# RoverWing-cover-V1_5.net
KiCad netlist of a schematic drawn in EAGLE
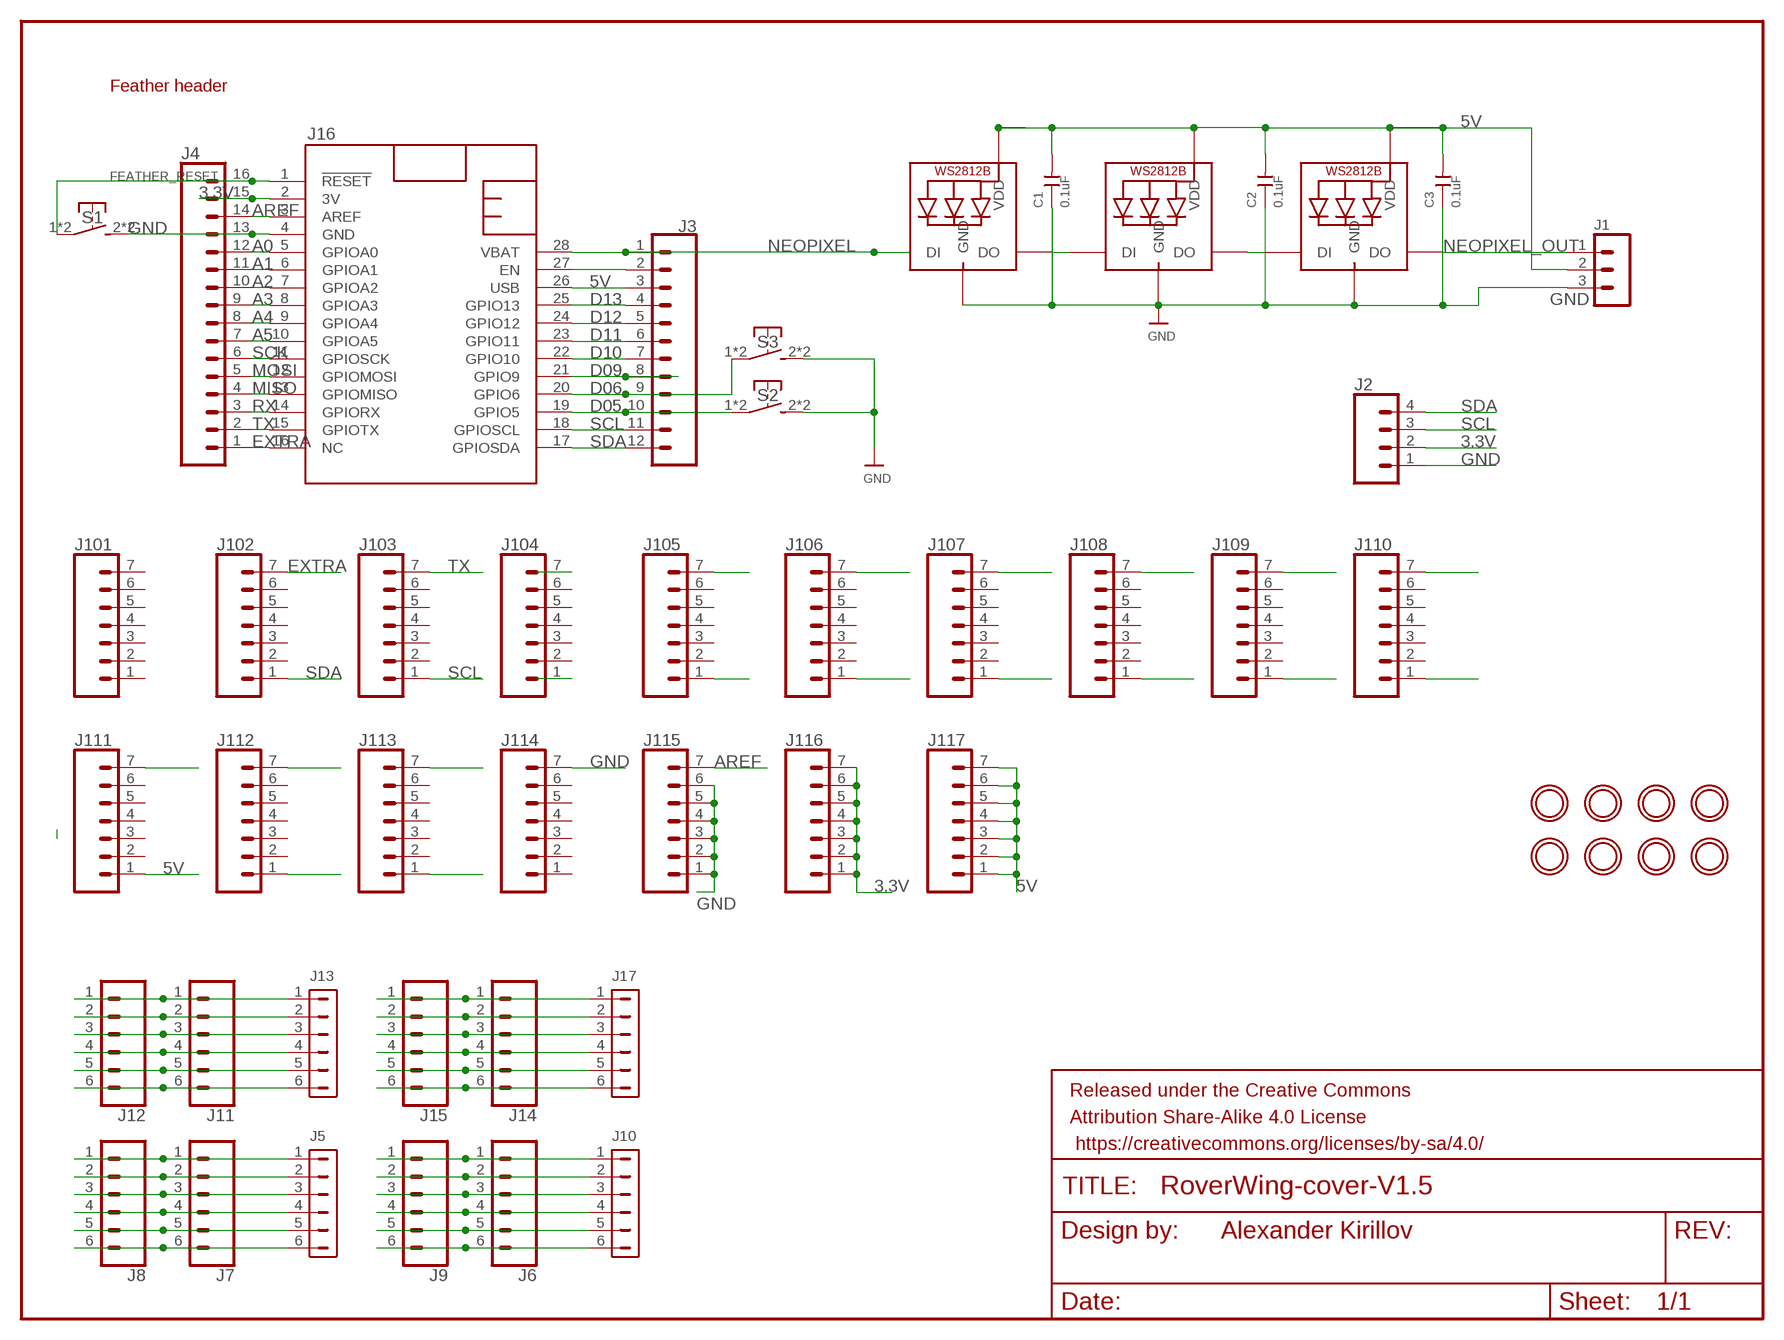
[diagram p0: schematic, sheet 1]

(export (version "E")
  (design (tool "Eeschema 10.0.6"))
  (components
    (comp (ref "C1")
      (value "0.1uF")
      (footprint "eagle-import:C0805")
      (libsource (lib "eagle-import") (part "CAP-CERAMIC-SMD-0805"))
    )
    (comp (ref "C2")
      (value "0.1uF")
      (footprint "eagle-import:C0805")
      (libsource (lib "eagle-import") (part "CAP-CERAMIC-SMD-0805"))
    )
    (comp (ref "C3")
      (value "0.1uF")
      (footprint "eagle-import:C0805")
      (libsource (lib "eagle-import") (part "CAP-CERAMIC-SMD-0805"))
    )
    (comp (ref "FRAME2")
      (value "FRAME-LETTERNO_PACKAGE")
      (footprint "eagle-import:DUMMY")
      (fields (field (name "DESIGNER") "Nobody"))
      (libsource (lib "eagle-import") (part "FRAME-LETTERNO_PACKAGE"))
    )
    (comp (ref "J1")
      (value "HEADER-PH-3PSIDEENTRY")
      (footprint "eagle-import:S3B-PH-K")
      (fields (field (name "PARTNO") "S3B-PH-K-S(LF)(SN)"))
      (libsource (lib "eagle-import") (part "HEADER-PH-3PSIDEENTRY"))
    )
    (comp (ref "J2")
      (value "CONN_04")
      (footprint "eagle-import:1X04")
      (libsource (lib "eagle-import") (part "CONN_04"))
    )
    (comp (ref "J3")
      (value "CONN_12NO_SILK")
      (footprint "eagle-import:1X12_NO_SILK")
      (libsource (lib "eagle-import") (part "CONN_12NO_SILK"))
    )
    (comp (ref "J4")
      (value "CONN_161X16_NO_SILK")
      (footprint "eagle-import:1X16_NO_SILK")
      (libsource (lib "eagle-import") (part "CONN_161X16_NO_SILK"))
    )
    (comp (ref "J5")
      (value "HEADER-PH-6PSIDEENTRY")
      (footprint "eagle-import:S6B-PH-K")
      (libsource (lib "eagle-import") (part "HEADER-PH-6PSIDEENTRY"))
    )
    (comp (ref "J6")
      (value "CONN_06NO_SILK_NO_POP")
      (footprint "eagle-import:1X06_NO_SILK")
      (libsource (lib "eagle-import") (part "CONN_06NO_SILK_NO_POP"))
    )
    (comp (ref "J7")
      (value "CONN_06NO_SILK_NO_POP")
      (footprint "eagle-import:1X06_NO_SILK")
      (libsource (lib "eagle-import") (part "CONN_06NO_SILK_NO_POP"))
    )
    (comp (ref "J8")
      (value "CONN_06NO_SILK_NO_POP")
      (footprint "eagle-import:1X06_NO_SILK")
      (libsource (lib "eagle-import") (part "CONN_06NO_SILK_NO_POP"))
    )
    (comp (ref "J9")
      (value "CONN_06NO_SILK_NO_POP")
      (footprint "eagle-import:1X06_NO_SILK")
      (libsource (lib "eagle-import") (part "CONN_06NO_SILK_NO_POP"))
    )
    (comp (ref "J10")
      (value "HEADER-PH-6PSIDEENTRY")
      (footprint "eagle-import:S6B-PH-K")
      (libsource (lib "eagle-import") (part "HEADER-PH-6PSIDEENTRY"))
    )
    (comp (ref "J11")
      (value "CONN_06NO_SILK_NO_POP")
      (footprint "eagle-import:1X06_NO_SILK")
      (libsource (lib "eagle-import") (part "CONN_06NO_SILK_NO_POP"))
    )
    (comp (ref "J12")
      (value "CONN_06NO_SILK_NO_POP")
      (footprint "eagle-import:1X06_NO_SILK")
      (libsource (lib "eagle-import") (part "CONN_06NO_SILK_NO_POP"))
    )
    (comp (ref "J13")
      (value "HEADER-PH-6PSIDEENTRY")
      (footprint "eagle-import:S6B-PH-K")
      (libsource (lib "eagle-import") (part "HEADER-PH-6PSIDEENTRY"))
    )
    (comp (ref "J14")
      (value "CONN_06NO_SILK_NO_POP")
      (footprint "eagle-import:1X06_NO_SILK")
      (libsource (lib "eagle-import") (part "CONN_06NO_SILK_NO_POP"))
    )
    (comp (ref "J15")
      (value "CONN_06NO_SILK_NO_POP")
      (footprint "eagle-import:1X06_NO_SILK")
      (libsource (lib "eagle-import") (part "CONN_06NO_SILK_NO_POP"))
    )
    (comp (ref "J16")
      (value "FEATHERWING_NODIM")
      (footprint "eagle-import:FEATHERWING_DIM")
      (libsource (lib "eagle-import") (part "FEATHERWING_NODIM"))
    )
    (comp (ref "J17")
      (value "HEADER-PH-6PSIDEENTRY")
      (footprint "eagle-import:S6B-PH-K")
      (libsource (lib "eagle-import") (part "HEADER-PH-6PSIDEENTRY"))
    )
    (comp (ref "J101")
      (value "CONN_07NO_SILK")
      (footprint "eagle-import:1X07_NO_SILK")
      (libsource (lib "eagle-import") (part "CONN_07NO_SILK"))
    )
    (comp (ref "J102")
      (value "CONN_07NO_SILK")
      (footprint "eagle-import:1X07_NO_SILK")
      (libsource (lib "eagle-import") (part "CONN_07NO_SILK"))
    )
    (comp (ref "J103")
      (value "CONN_07NO_SILK")
      (footprint "eagle-import:1X07_NO_SILK")
      (libsource (lib "eagle-import") (part "CONN_07NO_SILK"))
    )
    (comp (ref "J104")
      (value "CONN_07NO_SILK")
      (footprint "eagle-import:1X07_NO_SILK")
      (libsource (lib "eagle-import") (part "CONN_07NO_SILK"))
    )
    (comp (ref "J105")
      (value "CONN_07NO_SILK")
      (footprint "eagle-import:1X07_NO_SILK")
      (libsource (lib "eagle-import") (part "CONN_07NO_SILK"))
    )
    (comp (ref "J106")
      (value "CONN_07NO_SILK")
      (footprint "eagle-import:1X07_NO_SILK")
      (libsource (lib "eagle-import") (part "CONN_07NO_SILK"))
    )
    (comp (ref "J107")
      (value "CONN_07NO_SILK")
      (footprint "eagle-import:1X07_NO_SILK")
      (libsource (lib "eagle-import") (part "CONN_07NO_SILK"))
    )
    (comp (ref "J108")
      (value "CONN_07NO_SILK")
      (footprint "eagle-import:1X07_NO_SILK")
      (libsource (lib "eagle-import") (part "CONN_07NO_SILK"))
    )
    (comp (ref "J109")
      (value "CONN_07NO_SILK")
      (footprint "eagle-import:1X07_NO_SILK")
      (libsource (lib "eagle-import") (part "CONN_07NO_SILK"))
    )
    (comp (ref "J110")
      (value "CONN_07NO_SILK")
      (footprint "eagle-import:1X07_NO_SILK")
      (libsource (lib "eagle-import") (part "CONN_07NO_SILK"))
    )
    (comp (ref "J111")
      (value "CONN_07NO_SILK")
      (footprint "eagle-import:1X07_NO_SILK")
      (libsource (lib "eagle-import") (part "CONN_07NO_SILK"))
    )
    (comp (ref "J112")
      (value "CONN_07NO_SILK")
      (footprint "eagle-import:1X07_NO_SILK")
      (libsource (lib "eagle-import") (part "CONN_07NO_SILK"))
    )
    (comp (ref "J113")
      (value "CONN_07NO_SILK")
      (footprint "eagle-import:1X07_NO_SILK")
      (libsource (lib "eagle-import") (part "CONN_07NO_SILK"))
    )
    (comp (ref "J114")
      (value "CONN_07NO_SILK")
      (footprint "eagle-import:1X07_NO_SILK")
      (libsource (lib "eagle-import") (part "CONN_07NO_SILK"))
    )
    (comp (ref "J115")
      (value "CONN_07NO_SILK")
      (footprint "eagle-import:1X07_NO_SILK")
      (libsource (lib "eagle-import") (part "CONN_07NO_SILK"))
    )
    (comp (ref "J116")
      (value "CONN_07NO_SILK")
      (footprint "eagle-import:1X07_NO_SILK")
      (libsource (lib "eagle-import") (part "CONN_07NO_SILK"))
    )
    (comp (ref "J117")
      (value "CONN_07NO_SILK")
      (footprint "eagle-import:1X07_NO_SILK")
      (libsource (lib "eagle-import") (part "CONN_07NO_SILK"))
    )
    (comp (ref "LED1")
      (value "WS2812B5050")
      (footprint "eagle-import:WS2812B")
      (libsource (lib "eagle-import") (part "WS2812B5050"))
    )
    (comp (ref "LED2")
      (value "WS2812B5050")
      (footprint "eagle-import:WS2812B")
      (libsource (lib "eagle-import") (part "WS2812B5050"))
    )
    (comp (ref "LED3")
      (value "WS2812B5050")
      (footprint "eagle-import:WS2812B")
      (libsource (lib "eagle-import") (part "WS2812B5050"))
    )
    (comp (ref "S1")
      (value "SW-TACTILE-4.5X4.5_SMD")
      (footprint "eagle-import:TL3305")
      (libsource (lib "eagle-import") (part "SW-TACTILE-4.5X4.5_SMD"))
    )
    (comp (ref "S2")
      (value "SW-TACTILE-4.5X4.5_SMD")
      (footprint "eagle-import:TL3305")
      (libsource (lib "eagle-import") (part "SW-TACTILE-4.5X4.5_SMD"))
    )
    (comp (ref "S3")
      (value "SW-TACTILE-4.5X4.5_SMD")
      (footprint "eagle-import:TL3305")
      (libsource (lib "eagle-import") (part "SW-TACTILE-4.5X4.5_SMD"))
    )
    (comp (ref "U$3")
      (value "MOUNTINGHOLE3.0_NPH")
      (footprint "eagle-import:MOUNTINGHOLE_3.0_NPH")
      (libsource (lib "eagle-import") (part "MOUNTINGHOLE3.0_NPH"))
    )
    (comp (ref "U$4")
      (value "MOUNTINGHOLE3.0_NPH")
      (footprint "eagle-import:MOUNTINGHOLE_3.0_NPH")
      (libsource (lib "eagle-import") (part "MOUNTINGHOLE3.0_NPH"))
    )
    (comp (ref "U$14")
      (value "MOUNTINGHOLE3.0_NPH")
      (footprint "eagle-import:MOUNTINGHOLE_3.0_NPH")
      (libsource (lib "eagle-import") (part "MOUNTINGHOLE3.0_NPH"))
    )
    (comp (ref "U$15")
      (value "MOUNTINGHOLE3.0_NPH")
      (footprint "eagle-import:MOUNTINGHOLE_3.0_NPH")
      (libsource (lib "eagle-import") (part "MOUNTINGHOLE3.0_NPH"))
    )
    (comp (ref "U$24")
      (value "MOUNTINGHOLE3.0_NPH")
      (footprint "eagle-import:MOUNTINGHOLE_3.0_NPH")
      (libsource (lib "eagle-import") (part "MOUNTINGHOLE3.0_NPH"))
    )
    (comp (ref "U$25")
      (value "MOUNTINGHOLE3.0_NPH")
      (footprint "eagle-import:MOUNTINGHOLE_3.0_NPH")
      (libsource (lib "eagle-import") (part "MOUNTINGHOLE3.0_NPH"))
    )
    (comp (ref "U$26")
      (value "MOUNTINGHOLE3.0_NPH")
      (footprint "eagle-import:MOUNTINGHOLE_3.0_NPH")
      (libsource (lib "eagle-import") (part "MOUNTINGHOLE3.0_NPH"))
    )
    (comp (ref "U$27")
      (value "MOUNTINGHOLE3.0_NPH")
      (footprint "eagle-import:MOUNTINGHOLE_3.0_NPH")
      (libsource (lib "eagle-import") (part "MOUNTINGHOLE3.0_NPH"))
    )
  )
  (nets
    (net (code "1") (name "/3.3V") (class "Default")
      (node (ref "J116") (pin "1") (pinfunction "1_1") (pintype "passive"))
      (node (ref "J116") (pin "2") (pinfunction "2_2") (pintype "passive"))
      (node (ref "J116") (pin "3") (pinfunction "3_3") (pintype "passive"))
      (node (ref "J116") (pin "4") (pinfunction "4_4") (pintype "passive"))
      (node (ref "J116") (pin "5") (pinfunction "5_5") (pintype "passive"))
      (node (ref "J116") (pin "6") (pinfunction "6_6") (pintype "passive"))
      (node (ref "J116") (pin "7") (pinfunction "7_7") (pintype "passive"))
      (node (ref "J16") (pin "2") (pinfunction "3V_2") (pintype "power_in"))
      (node (ref "J2") (pin "2") (pinfunction "2_2") (pintype "passive"))
      (node (ref "J4") (pin "15") (pinfunction "15_15") (pintype "passive"))
    )
    (net (code "2") (name "/5V") (class "Default")
      (node (ref "C1") (pin "2") (pinfunction "2_2") (pintype "passive"))
      (node (ref "C2") (pin "2") (pinfunction "2_2") (pintype "passive"))
      (node (ref "C3") (pin "2") (pinfunction "2_2") (pintype "passive"))
      (node (ref "J1") (pin "2") (pinfunction "2_2") (pintype "passive"))
      (node (ref "J111") (pin "1") (pinfunction "1_1") (pintype "passive"))
      (node (ref "J117") (pin "1") (pinfunction "1_1") (pintype "passive"))
      (node (ref "J117") (pin "2") (pinfunction "2_2") (pintype "passive"))
      (node (ref "J117") (pin "3") (pinfunction "3_3") (pintype "passive"))
      (node (ref "J117") (pin "4") (pinfunction "4_4") (pintype "passive"))
      (node (ref "J117") (pin "5") (pinfunction "5_5") (pintype "passive"))
      (node (ref "J117") (pin "6") (pinfunction "6_6") (pintype "passive"))
      (node (ref "J117") (pin "7") (pinfunction "7_7") (pintype "passive"))
      (node (ref "J16") (pin "26") (pinfunction "USB_26") (pintype "power_in"))
      (node (ref "J3") (pin "3") (pinfunction "3_3") (pintype "passive"))
      (node (ref "LED1") (pin "1-VDD") (pinfunction "VDD_1-VDD") (pintype "power_in"))
      (node (ref "LED2") (pin "1-VDD") (pinfunction "VDD_1-VDD") (pintype "power_in"))
      (node (ref "LED3") (pin "1-VDD") (pinfunction "VDD_1-VDD") (pintype "power_in"))
    )
    (net (code "3") (name "/A0") (class "Default")
      (node (ref "J113") (pin "7") (pinfunction "7_7") (pintype "passive"))
      (node (ref "J16") (pin "5") (pinfunction "GPIOA0_5") (pintype "bidirectional"))
      (node (ref "J4") (pin "12") (pinfunction "12_12") (pintype "passive"))
    )
    (net (code "4") (name "/A1") (class "Default")
      (node (ref "J112") (pin "7") (pinfunction "7_7") (pintype "passive"))
      (node (ref "J16") (pin "6") (pinfunction "GPIOA1_6") (pintype "bidirectional"))
      (node (ref "J4") (pin "11") (pinfunction "11_11") (pintype "passive"))
    )
    (net (code "5") (name "/A2") (class "Default")
      (node (ref "J111") (pin "7") (pinfunction "7_7") (pintype "passive"))
      (node (ref "J16") (pin "7") (pinfunction "GPIOA2_7") (pintype "bidirectional"))
      (node (ref "J4") (pin "10") (pinfunction "10_10") (pintype "passive"))
    )
    (net (code "6") (name "/A3") (class "Default")
      (node (ref "J110") (pin "7") (pinfunction "7_7") (pintype "passive"))
      (node (ref "J16") (pin "8") (pinfunction "GPIOA3_8") (pintype "bidirectional"))
      (node (ref "J4") (pin "9") (pinfunction "9_9") (pintype "passive"))
    )
    (net (code "7") (name "/A4") (class "Default")
      (node (ref "J109") (pin "7") (pinfunction "7_7") (pintype "passive"))
      (node (ref "J16") (pin "9") (pinfunction "GPIOA4_9") (pintype "bidirectional"))
      (node (ref "J4") (pin "8") (pinfunction "8_8") (pintype "passive"))
    )
    (net (code "8") (name "/A5") (class "Default")
      (node (ref "J108") (pin "7") (pinfunction "7_7") (pintype "passive"))
      (node (ref "J16") (pin "10") (pinfunction "GPIOA5_10") (pintype "bidirectional"))
      (node (ref "J4") (pin "7") (pinfunction "7_7") (pintype "passive"))
    )
    (net (code "9") (name "/AREF") (class "Default")
      (node (ref "J115") (pin "7") (pinfunction "7_7") (pintype "passive"))
      (node (ref "J16") (pin "3") (pinfunction "AREF_3") (pintype "passive"))
      (node (ref "J4") (pin "14") (pinfunction "14_14") (pintype "passive"))
    )
    (net (code "10") (name "/D05") (class "Default")
      (node (ref "J104") (pin "1") (pinfunction "1_1") (pintype "passive"))
      (node (ref "J16") (pin "19") (pinfunction "GPIO5_19") (pintype "bidirectional"))
      (node (ref "J3") (pin "10") (pinfunction "10_10") (pintype "passive"))
      (node (ref "S2") (pin "1") (pinfunction "P1_1") (pintype "passive"))
      (node (ref "S2") (pin "4") (pinfunction "P1_4") (pintype "passive"))
    )
    (net (code "11") (name "/D06") (class "Default")
      (node (ref "J105") (pin "1") (pinfunction "1_1") (pintype "passive"))
      (node (ref "J16") (pin "20") (pinfunction "GPIO6_20") (pintype "bidirectional"))
      (node (ref "J3") (pin "9") (pinfunction "9_9") (pintype "passive"))
      (node (ref "S3") (pin "1") (pinfunction "P1_1") (pintype "passive"))
      (node (ref "S3") (pin "4") (pinfunction "P1_4") (pintype "passive"))
    )
    (net (code "12") (name "/D09") (class "Default")
      (node (ref "J106") (pin "1") (pinfunction "1_1") (pintype "passive"))
      (node (ref "J16") (pin "21") (pinfunction "GPIO9_21") (pintype "bidirectional"))
      (node (ref "J3") (pin "8") (pinfunction "8_8") (pintype "passive"))
    )
    (net (code "13") (name "/D10") (class "Default")
      (node (ref "J107") (pin "1") (pinfunction "1_1") (pintype "passive"))
      (node (ref "J16") (pin "22") (pinfunction "GPIO10_22") (pintype "bidirectional"))
      (node (ref "J3") (pin "7") (pinfunction "7_7") (pintype "passive"))
    )
    (net (code "14") (name "/D11") (class "Default")
      (node (ref "J108") (pin "1") (pinfunction "1_1") (pintype "passive"))
      (node (ref "J16") (pin "23") (pinfunction "GPIO11_23") (pintype "bidirectional"))
      (node (ref "J3") (pin "6") (pinfunction "6_6") (pintype "passive"))
    )
    (net (code "15") (name "/D12") (class "Default")
      (node (ref "J109") (pin "1") (pinfunction "1_1") (pintype "passive"))
      (node (ref "J16") (pin "24") (pinfunction "GPIO12_24") (pintype "bidirectional"))
      (node (ref "J3") (pin "5") (pinfunction "5_5") (pintype "passive"))
    )
    (net (code "16") (name "/D13") (class "Default")
      (node (ref "J110") (pin "1") (pinfunction "1_1") (pintype "passive"))
      (node (ref "J16") (pin "25") (pinfunction "GPIO13_25") (pintype "bidirectional"))
      (node (ref "J3") (pin "4") (pinfunction "4_4") (pintype "passive"))
    )
    (net (code "17") (name "/EXTRA") (class "Default")
      (node (ref "J102") (pin "7") (pinfunction "7_7") (pintype "passive"))
      (node (ref "J16") (pin "16") (pinfunction "NC_16") (pintype "passive"))
      (node (ref "J4") (pin "1") (pinfunction "1_1") (pintype "passive"))
    )
    (net (code "18") (name "/FEATHER_RESET") (class "Default")
      (node (ref "J16") (pin "1") (pinfunction "~{RESET}_1") (pintype "input"))
      (node (ref "J4") (pin "16") (pinfunction "16_16") (pintype "passive"))
      (node (ref "S1") (pin "1") (pinfunction "P1_1") (pintype "passive"))
      (node (ref "S1") (pin "4") (pinfunction "P1_4") (pintype "passive"))
    )
    (net (code "19") (name "/MISO") (class "Default")
      (node (ref "J105") (pin "7") (pinfunction "7_7") (pintype "passive"))
      (node (ref "J16") (pin "13") (pinfunction "GPIOMISO_13") (pintype "bidirectional"))
      (node (ref "J4") (pin "4") (pinfunction "4_4") (pintype "passive"))
    )
    (net (code "20") (name "/MOSI") (class "Default")
      (node (ref "J106") (pin "7") (pinfunction "7_7") (pintype "passive"))
      (node (ref "J16") (pin "12") (pinfunction "GPIOMOSI_12") (pintype "bidirectional"))
      (node (ref "J4") (pin "5") (pinfunction "5_5") (pintype "passive"))
    )
    (net (code "21") (name "/N$37") (class "Default")
      (node (ref "J112") (pin "1") (pinfunction "1_1") (pintype "passive"))
      (node (ref "J16") (pin "27") (pinfunction "EN_27") (pintype "passive"))
      (node (ref "J3") (pin "2") (pinfunction "2_2") (pintype "passive"))
    )
    (net (code "22") (name "/NEOPIXEL") (class "Default")
      (node (ref "J16") (pin "28") (pinfunction "VBAT_28") (pintype "power_in"))
      (node (ref "J3") (pin "1") (pinfunction "1_1") (pintype "passive"))
      (node (ref "LED1") (pin "4-DIN") (pinfunction "DI_4-DIN") (pintype "input"))
    )
    (net (code "23") (name "/NEOPIXEL_OUT") (class "Default")
      (node (ref "J1") (pin "1") (pinfunction "1_1") (pintype "passive"))
      (node (ref "LED3") (pin "2-DOUT") (pinfunction "DO_2-DOUT") (pintype "output"))
    )
    (net (code "24") (name "/RX") (class "Default")
      (node (ref "J104") (pin "7") (pinfunction "7_7") (pintype "passive"))
      (node (ref "J16") (pin "14") (pinfunction "GPIORX_14") (pintype "bidirectional"))
      (node (ref "J4") (pin "3") (pinfunction "3_3") (pintype "passive"))
    )
    (net (code "25") (name "/SCK") (class "Default")
      (node (ref "J107") (pin "7") (pinfunction "7_7") (pintype "passive"))
      (node (ref "J16") (pin "11") (pinfunction "GPIOSCK_11") (pintype "bidirectional"))
      (node (ref "J4") (pin "6") (pinfunction "6_6") (pintype "passive"))
    )
    (net (code "26") (name "/SCL") (class "Default")
      (node (ref "J103") (pin "1") (pinfunction "1_1") (pintype "passive"))
      (node (ref "J16") (pin "18") (pinfunction "GPIOSCL_18") (pintype "bidirectional"))
      (node (ref "J2") (pin "3") (pinfunction "3_3") (pintype "passive"))
      (node (ref "J3") (pin "11") (pinfunction "11_11") (pintype "passive"))
    )
    (net (code "27") (name "/SDA") (class "Default")
      (node (ref "J102") (pin "1") (pinfunction "1_1") (pintype "passive"))
      (node (ref "J16") (pin "17") (pinfunction "GPIOSDA_17") (pintype "bidirectional"))
      (node (ref "J2") (pin "4") (pinfunction "4_4") (pintype "passive"))
      (node (ref "J3") (pin "12") (pinfunction "12_12") (pintype "passive"))
    )
    (net (code "28") (name "/TX") (class "Default")
      (node (ref "J103") (pin "7") (pinfunction "7_7") (pintype "passive"))
      (node (ref "J16") (pin "15") (pinfunction "GPIOTX_15") (pintype "bidirectional"))
      (node (ref "J4") (pin "2") (pinfunction "2_2") (pintype "passive"))
    )
    (net (code "29") (name "GND") (class "Default")
      (node (ref "C1") (pin "1") (pinfunction "1_1") (pintype "passive"))
      (node (ref "C2") (pin "1") (pinfunction "1_1") (pintype "passive"))
      (node (ref "C3") (pin "1") (pinfunction "1_1") (pintype "passive"))
      (node (ref "J1") (pin "3") (pinfunction "3_3") (pintype "passive"))
      (node (ref "J114") (pin "7") (pinfunction "7_7") (pintype "passive"))
      (node (ref "J115") (pin "1") (pinfunction "1_1") (pintype "passive"))
      (node (ref "J115") (pin "2") (pinfunction "2_2") (pintype "passive"))
      (node (ref "J115") (pin "3") (pinfunction "3_3") (pintype "passive"))
      (node (ref "J115") (pin "4") (pinfunction "4_4") (pintype "passive"))
      (node (ref "J115") (pin "5") (pinfunction "5_5") (pintype "passive"))
      (node (ref "J115") (pin "6") (pinfunction "6_6") (pintype "passive"))
      (node (ref "J16") (pin "4") (pinfunction "GND_4") (pintype "power_in"))
      (node (ref "J2") (pin "1") (pinfunction "1_1") (pintype "passive"))
      (node (ref "J4") (pin "13") (pinfunction "13_13") (pintype "passive"))
      (node (ref "LED1") (pin "3-GND") (pinfunction "GND_3-GND") (pintype "power_in"))
      (node (ref "LED2") (pin "3-GND") (pinfunction "GND_3-GND") (pintype "power_in"))
      (node (ref "LED3") (pin "3-GND") (pinfunction "GND_3-GND") (pintype "power_in"))
      (node (ref "S1") (pin "2") (pinfunction "S1_2") (pintype "passive"))
      (node (ref "S1") (pin "3") (pinfunction "S1_3") (pintype "passive"))
      (node (ref "S2") (pin "2") (pinfunction "S1_2") (pintype "passive"))
      (node (ref "S2") (pin "3") (pinfunction "S1_3") (pintype "passive"))
      (node (ref "S3") (pin "2") (pinfunction "S1_2") (pintype "passive"))
      (node (ref "S3") (pin "3") (pinfunction "S1_3") (pintype "passive"))
    )
    (net (code "30") (name "Net-(J5-Pad1)") (class "Default")
      (node (ref "J5") (pin "1") (pinfunction "1_1") (pintype "passive"))
      (node (ref "J7") (pin "1") (pinfunction "1_1") (pintype "passive"))
      (node (ref "J8") (pin "1") (pinfunction "1_1") (pintype "passive"))
    )
    (net (code "31") (name "Net-(J5-Pad2)") (class "Default")
      (node (ref "J5") (pin "2") (pinfunction "2_2") (pintype "passive"))
      (node (ref "J7") (pin "2") (pinfunction "2_2") (pintype "passive"))
      (node (ref "J8") (pin "2") (pinfunction "2_2") (pintype "passive"))
    )
    (net (code "32") (name "Net-(J5-Pad3)") (class "Default")
      (node (ref "J5") (pin "3") (pinfunction "3_3") (pintype "passive"))
      (node (ref "J7") (pin "3") (pinfunction "3_3") (pintype "passive"))
      (node (ref "J8") (pin "3") (pinfunction "3_3") (pintype "passive"))
    )
    (net (code "33") (name "Net-(J5-Pad4)") (class "Default")
      (node (ref "J5") (pin "4") (pinfunction "4_4") (pintype "passive"))
      (node (ref "J7") (pin "4") (pinfunction "4_4") (pintype "passive"))
      (node (ref "J8") (pin "4") (pinfunction "4_4") (pintype "passive"))
    )
    (net (code "34") (name "Net-(J5-Pad5)") (class "Default")
      (node (ref "J5") (pin "5") (pinfunction "5_5") (pintype "passive"))
      (node (ref "J7") (pin "5") (pinfunction "5_5") (pintype "passive"))
      (node (ref "J8") (pin "5") (pinfunction "5_5") (pintype "passive"))
    )
    (net (code "35") (name "Net-(J5-Pad6)") (class "Default")
      (node (ref "J5") (pin "6") (pinfunction "6_6") (pintype "passive"))
      (node (ref "J7") (pin "6") (pinfunction "6_6") (pintype "passive"))
      (node (ref "J8") (pin "6") (pinfunction "6_6") (pintype "passive"))
    )
    (net (code "36") (name "Net-(J10-Pad1)") (class "Default")
      (node (ref "J10") (pin "1") (pinfunction "1_1") (pintype "passive"))
      (node (ref "J6") (pin "1") (pinfunction "1_1") (pintype "passive"))
      (node (ref "J9") (pin "1") (pinfunction "1_1") (pintype "passive"))
    )
    (net (code "37") (name "Net-(J10-Pad2)") (class "Default")
      (node (ref "J10") (pin "2") (pinfunction "2_2") (pintype "passive"))
      (node (ref "J6") (pin "2") (pinfunction "2_2") (pintype "passive"))
      (node (ref "J9") (pin "2") (pinfunction "2_2") (pintype "passive"))
    )
    (net (code "38") (name "Net-(J10-Pad3)") (class "Default")
      (node (ref "J10") (pin "3") (pinfunction "3_3") (pintype "passive"))
      (node (ref "J6") (pin "3") (pinfunction "3_3") (pintype "passive"))
      (node (ref "J9") (pin "3") (pinfunction "3_3") (pintype "passive"))
    )
    (net (code "39") (name "Net-(J10-Pad4)") (class "Default")
      (node (ref "J10") (pin "4") (pinfunction "4_4") (pintype "passive"))
      (node (ref "J6") (pin "4") (pinfunction "4_4") (pintype "passive"))
      (node (ref "J9") (pin "4") (pinfunction "4_4") (pintype "passive"))
    )
    (net (code "40") (name "Net-(J10-Pad5)") (class "Default")
      (node (ref "J10") (pin "5") (pinfunction "5_5") (pintype "passive"))
      (node (ref "J6") (pin "5") (pinfunction "5_5") (pintype "passive"))
      (node (ref "J9") (pin "5") (pinfunction "5_5") (pintype "passive"))
    )
    (net (code "41") (name "Net-(J10-Pad6)") (class "Default")
      (node (ref "J10") (pin "6") (pinfunction "6_6") (pintype "passive"))
      (node (ref "J6") (pin "6") (pinfunction "6_6") (pintype "passive"))
      (node (ref "J9") (pin "6") (pinfunction "6_6") (pintype "passive"))
    )
    (net (code "42") (name "Net-(J11-Pad1)") (class "Default")
      (node (ref "J11") (pin "1") (pinfunction "1_1") (pintype "passive"))
      (node (ref "J12") (pin "1") (pinfunction "1_1") (pintype "passive"))
      (node (ref "J13") (pin "1") (pinfunction "1_1") (pintype "passive"))
    )
    (net (code "43") (name "Net-(J11-Pad2)") (class "Default")
      (node (ref "J11") (pin "2") (pinfunction "2_2") (pintype "passive"))
      (node (ref "J12") (pin "2") (pinfunction "2_2") (pintype "passive"))
      (node (ref "J13") (pin "2") (pinfunction "2_2") (pintype "passive"))
    )
    (net (code "44") (name "Net-(J11-Pad3)") (class "Default")
      (node (ref "J11") (pin "3") (pinfunction "3_3") (pintype "passive"))
      (node (ref "J12") (pin "3") (pinfunction "3_3") (pintype "passive"))
      (node (ref "J13") (pin "3") (pinfunction "3_3") (pintype "passive"))
    )
    (net (code "45") (name "Net-(J11-Pad4)") (class "Default")
      (node (ref "J11") (pin "4") (pinfunction "4_4") (pintype "passive"))
      (node (ref "J12") (pin "4") (pinfunction "4_4") (pintype "passive"))
      (node (ref "J13") (pin "4") (pinfunction "4_4") (pintype "passive"))
    )
    (net (code "46") (name "Net-(J11-Pad5)") (class "Default")
      (node (ref "J11") (pin "5") (pinfunction "5_5") (pintype "passive"))
      (node (ref "J12") (pin "5") (pinfunction "5_5") (pintype "passive"))
      (node (ref "J13") (pin "5") (pinfunction "5_5") (pintype "passive"))
    )
    (net (code "47") (name "Net-(J11-Pad6)") (class "Default")
      (node (ref "J11") (pin "6") (pinfunction "6_6") (pintype "passive"))
      (node (ref "J12") (pin "6") (pinfunction "6_6") (pintype "passive"))
      (node (ref "J13") (pin "6") (pinfunction "6_6") (pintype "passive"))
    )
    (net (code "48") (name "Net-(J14-Pad1)") (class "Default")
      (node (ref "J14") (pin "1") (pinfunction "1_1") (pintype "passive"))
      (node (ref "J15") (pin "1") (pinfunction "1_1") (pintype "passive"))
      (node (ref "J17") (pin "1") (pinfunction "1_1") (pintype "passive"))
    )
    (net (code "49") (name "Net-(J14-Pad2)") (class "Default")
      (node (ref "J14") (pin "2") (pinfunction "2_2") (pintype "passive"))
      (node (ref "J15") (pin "2") (pinfunction "2_2") (pintype "passive"))
      (node (ref "J17") (pin "2") (pinfunction "2_2") (pintype "passive"))
    )
    (net (code "50") (name "Net-(J14-Pad3)") (class "Default")
      (node (ref "J14") (pin "3") (pinfunction "3_3") (pintype "passive"))
      (node (ref "J15") (pin "3") (pinfunction "3_3") (pintype "passive"))
      (node (ref "J17") (pin "3") (pinfunction "3_3") (pintype "passive"))
    )
    (net (code "51") (name "Net-(J14-Pad4)") (class "Default")
      (node (ref "J14") (pin "4") (pinfunction "4_4") (pintype "passive"))
      (node (ref "J15") (pin "4") (pinfunction "4_4") (pintype "passive"))
      (node (ref "J17") (pin "4") (pinfunction "4_4") (pintype "passive"))
    )
    (net (code "52") (name "Net-(J14-Pad5)") (class "Default")
      (node (ref "J14") (pin "5") (pinfunction "5_5") (pintype "passive"))
      (node (ref "J15") (pin "5") (pinfunction "5_5") (pintype "passive"))
      (node (ref "J17") (pin "5") (pinfunction "5_5") (pintype "passive"))
    )
    (net (code "53") (name "Net-(J14-Pad6)") (class "Default")
      (node (ref "J14") (pin "6") (pinfunction "6_6") (pintype "passive"))
      (node (ref "J15") (pin "6") (pinfunction "6_6") (pintype "passive"))
      (node (ref "J17") (pin "6") (pinfunction "6_6") (pintype "passive"))
    )
    (net (code "54") (name "Net-(LED1-DO)") (class "Default")
      (node (ref "LED1") (pin "2-DOUT") (pinfunction "DO_2-DOUT") (pintype "output"))
      (node (ref "LED2") (pin "4-DIN") (pinfunction "DI_4-DIN") (pintype "input"))
    )
    (net (code "55") (name "Net-(LED2-DO)") (class "Default")
      (node (ref "LED2") (pin "2-DOUT") (pinfunction "DO_2-DOUT") (pintype "output"))
      (node (ref "LED3") (pin "4-DIN") (pinfunction "DI_4-DIN") (pintype "input"))
    )
    (net (code "56") (name "unconnected-(J101-Pad1)") (class "Default")
      (node (ref "J101") (pin "1") (pinfunction "1_1") (pintype "passive"))
    )
    (net (code "57") (name "unconnected-(J101-Pad2)") (class "Default")
      (node (ref "J101") (pin "2") (pinfunction "2_2") (pintype "passive"))
    )
    (net (code "58") (name "unconnected-(J101-Pad3)") (class "Default")
      (node (ref "J101") (pin "3") (pinfunction "3_3") (pintype "passive"))
    )
    (net (code "59") (name "unconnected-(J101-Pad4)") (class "Default")
      (node (ref "J101") (pin "4") (pinfunction "4_4") (pintype "passive"))
    )
    (net (code "60") (name "unconnected-(J101-Pad5)") (class "Default")
      (node (ref "J101") (pin "5") (pinfunction "5_5") (pintype "passive"))
    )
    (net (code "61") (name "unconnected-(J101-Pad6)") (class "Default")
      (node (ref "J101") (pin "6") (pinfunction "6_6") (pintype "passive"))
    )
    (net (code "62") (name "unconnected-(J101-Pad7)") (class "Default")
      (node (ref "J101") (pin "7") (pinfunction "7_7") (pintype "passive"))
    )
    (net (code "63") (name "unconnected-(J102-Pad2)") (class "Default")
      (node (ref "J102") (pin "2") (pinfunction "2_2") (pintype "passive"))
    )
    (net (code "64") (name "unconnected-(J102-Pad3)") (class "Default")
      (node (ref "J102") (pin "3") (pinfunction "3_3") (pintype "passive"))
    )
    (net (code "65") (name "unconnected-(J102-Pad4)") (class "Default")
      (node (ref "J102") (pin "4") (pinfunction "4_4") (pintype "passive"))
    )
    (net (code "66") (name "unconnected-(J102-Pad5)") (class "Default")
      (node (ref "J102") (pin "5") (pinfunction "5_5") (pintype "passive"))
    )
    (net (code "67") (name "unconnected-(J102-Pad6)") (class "Default")
      (node (ref "J102") (pin "6") (pinfunction "6_6") (pintype "passive"))
    )
    (net (code "68") (name "unconnected-(J103-Pad2)") (class "Default")
      (node (ref "J103") (pin "2") (pinfunction "2_2") (pintype "passive"))
    )
    (net (code "69") (name "unconnected-(J103-Pad3)") (class "Default")
      (node (ref "J103") (pin "3") (pinfunction "3_3") (pintype "passive"))
    )
    (net (code "70") (name "unconnected-(J103-Pad4)") (class "Default")
      (node (ref "J103") (pin "4") (pinfunction "4_4") (pintype "passive"))
    )
    (net (code "71") (name "unconnected-(J103-Pad5)") (class "Default")
      (node (ref "J103") (pin "5") (pinfunction "5_5") (pintype "passive"))
    )
    (net (code "72") (name "unconnected-(J103-Pad6)") (class "Default")
      (node (ref "J103") (pin "6") (pinfunction "6_6") (pintype "passive"))
    )
    (net (code "73") (name "unconnected-(J104-Pad2)") (class "Default")
      (node (ref "J104") (pin "2") (pinfunction "2_2") (pintype "passive"))
    )
    (net (code "74") (name "unconnected-(J104-Pad3)") (class "Default")
      (node (ref "J104") (pin "3") (pinfunction "3_3") (pintype "passive"))
    )
    (net (code "75") (name "unconnected-(J104-Pad4)") (class "Default")
      (node (ref "J104") (pin "4") (pinfunction "4_4") (pintype "passive"))
    )
    (net (code "76") (name "unconnected-(J104-Pad5)") (class "Default")
      (node (ref "J104") (pin "5") (pinfunction "5_5") (pintype "passive"))
    )
    (net (code "77") (name "unconnected-(J104-Pad6)") (class "Default")
      (node (ref "J104") (pin "6") (pinfunction "6_6") (pintype "passive"))
    )
    (net (code "78") (name "unconnected-(J105-Pad2)") (class "Default")
      (node (ref "J105") (pin "2") (pinfunction "2_2") (pintype "passive"))
    )
    (net (code "79") (name "unconnected-(J105-Pad3)") (class "Default")
      (node (ref "J105") (pin "3") (pinfunction "3_3") (pintype "passive"))
    )
    (net (code "80") (name "unconnected-(J105-Pad4)") (class "Default")
      (node (ref "J105") (pin "4") (pinfunction "4_4") (pintype "passive"))
    )
    (net (code "81") (name "unconnected-(J105-Pad5)") (class "Default")
      (node (ref "J105") (pin "5") (pinfunction "5_5") (pintype "passive"))
    )
    (net (code "82") (name "unconnected-(J105-Pad6)") (class "Default")
      (node (ref "J105") (pin "6") (pinfunction "6_6") (pintype "passive"))
    )
    (net (code "83") (name "unconnected-(J106-Pad2)") (class "Default")
      (node (ref "J106") (pin "2") (pinfunction "2_2") (pintype "passive"))
    )
    (net (code "84") (name "unconnected-(J106-Pad3)") (class "Default")
      (node (ref "J106") (pin "3") (pinfunction "3_3") (pintype "passive"))
    )
    (net (code "85") (name "unconnected-(J106-Pad4)") (class "Default")
      (node (ref "J106") (pin "4") (pinfunction "4_4") (pintype "passive"))
    )
    (net (code "86") (name "unconnected-(J106-Pad5)") (class "Default")
      (node (ref "J106") (pin "5") (pinfunction "5_5") (pintype "passive"))
    )
    (net (code "87") (name "unconnected-(J106-Pad6)") (class "Default")
      (node (ref "J106") (pin "6") (pinfunction "6_6") (pintype "passive"))
    )
    (net (code "88") (name "unconnected-(J107-Pad2)") (class "Default")
      (node (ref "J107") (pin "2") (pinfunction "2_2") (pintype "passive"))
    )
    (net (code "89") (name "unconnected-(J107-Pad3)") (class "Default")
      (node (ref "J107") (pin "3") (pinfunction "3_3") (pintype "passive"))
    )
    (net (code "90") (name "unconnected-(J107-Pad4)") (class "Default")
      (node (ref "J107") (pin "4") (pinfunction "4_4") (pintype "passive"))
    )
    (net (code "91") (name "unconnected-(J107-Pad5)") (class "Default")
      (node (ref "J107") (pin "5") (pinfunction "5_5") (pintype "passive"))
    )
    (net (code "92") (name "unconnected-(J107-Pad6)") (class "Default")
      (node (ref "J107") (pin "6") (pinfunction "6_6") (pintype "passive"))
    )
    (net (code "93") (name "unconnected-(J108-Pad2)") (class "Default")
      (node (ref "J108") (pin "2") (pinfunction "2_2") (pintype "passive"))
    )
    (net (code "94") (name "unconnected-(J108-Pad3)") (class "Default")
      (node (ref "J108") (pin "3") (pinfunction "3_3") (pintype "passive"))
    )
    (net (code "95") (name "unconnected-(J108-Pad4)") (class "Default")
      (node (ref "J108") (pin "4") (pinfunction "4_4") (pintype "passive"))
    )
    (net (code "96") (name "unconnected-(J108-Pad5)") (class "Default")
      (node (ref "J108") (pin "5") (pinfunction "5_5") (pintype "passive"))
    )
    (net (code "97") (name "unconnected-(J108-Pad6)") (class "Default")
      (node (ref "J108") (pin "6") (pinfunction "6_6") (pintype "passive"))
    )
    (net (code "98") (name "unconnected-(J109-Pad2)") (class "Default")
      (node (ref "J109") (pin "2") (pinfunction "2_2") (pintype "passive"))
    )
    (net (code "99") (name "unconnected-(J109-Pad3)") (class "Default")
      (node (ref "J109") (pin "3") (pinfunction "3_3") (pintype "passive"))
    )
    (net (code "100") (name "unconnected-(J109-Pad4)") (class "Default")
      (node (ref "J109") (pin "4") (pinfunction "4_4") (pintype "passive"))
    )
    (net (code "101") (name "unconnected-(J109-Pad5)") (class "Default")
      (node (ref "J109") (pin "5") (pinfunction "5_5") (pintype "passive"))
    )
    (net (code "102") (name "unconnected-(J109-Pad6)") (class "Default")
      (node (ref "J109") (pin "6") (pinfunction "6_6") (pintype "passive"))
    )
    (net (code "103") (name "unconnected-(J110-Pad2)") (class "Default")
      (node (ref "J110") (pin "2") (pinfunction "2_2") (pintype "passive"))
    )
    (net (code "104") (name "unconnected-(J110-Pad3)") (class "Default")
      (node (ref "J110") (pin "3") (pinfunction "3_3") (pintype "passive"))
    )
    (net (code "105") (name "unconnected-(J110-Pad4)") (class "Default")
      (node (ref "J110") (pin "4") (pinfunction "4_4") (pintype "passive"))
    )
    (net (code "106") (name "unconnected-(J110-Pad5)") (class "Default")
      (node (ref "J110") (pin "5") (pinfunction "5_5") (pintype "passive"))
    )
    (net (code "107") (name "unconnected-(J110-Pad6)") (class "Default")
      (node (ref "J110") (pin "6") (pinfunction "6_6") (pintype "passive"))
    )
    (net (code "108") (name "unconnected-(J111-Pad2)") (class "Default")
      (node (ref "J111") (pin "2") (pinfunction "2_2") (pintype "passive"))
    )
    (net (code "109") (name "unconnected-(J111-Pad3)") (class "Default")
      (node (ref "J111") (pin "3") (pinfunction "3_3") (pintype "passive"))
    )
    (net (code "110") (name "unconnected-(J111-Pad4)") (class "Default")
      (node (ref "J111") (pin "4") (pinfunction "4_4") (pintype "passive"))
    )
    (net (code "111") (name "unconnected-(J111-Pad5)") (class "Default")
      (node (ref "J111") (pin "5") (pinfunction "5_5") (pintype "passive"))
    )
    (net (code "112") (name "unconnected-(J111-Pad6)") (class "Default")
      (node (ref "J111") (pin "6") (pinfunction "6_6") (pintype "passive"))
    )
    (net (code "113") (name "unconnected-(J112-Pad2)") (class "Default")
      (node (ref "J112") (pin "2") (pinfunction "2_2") (pintype "passive"))
    )
    (net (code "114") (name "unconnected-(J112-Pad3)") (class "Default")
      (node (ref "J112") (pin "3") (pinfunction "3_3") (pintype "passive"))
    )
    (net (code "115") (name "unconnected-(J112-Pad4)") (class "Default")
      (node (ref "J112") (pin "4") (pinfunction "4_4") (pintype "passive"))
    )
    (net (code "116") (name "unconnected-(J112-Pad5)") (class "Default")
      (node (ref "J112") (pin "5") (pinfunction "5_5") (pintype "passive"))
    )
    (net (code "117") (name "unconnected-(J112-Pad6)") (class "Default")
      (node (ref "J112") (pin "6") (pinfunction "6_6") (pintype "passive"))
    )
    (net (code "118") (name "unconnected-(J113-Pad1)") (class "Default")
      (node (ref "J113") (pin "1") (pinfunction "1_1") (pintype "passive"))
    )
    (net (code "119") (name "unconnected-(J113-Pad2)") (class "Default")
      (node (ref "J113") (pin "2") (pinfunction "2_2") (pintype "passive"))
    )
    (net (code "120") (name "unconnected-(J113-Pad3)") (class "Default")
      (node (ref "J113") (pin "3") (pinfunction "3_3") (pintype "passive"))
    )
    (net (code "121") (name "unconnected-(J113-Pad4)") (class "Default")
      (node (ref "J113") (pin "4") (pinfunction "4_4") (pintype "passive"))
    )
    (net (code "122") (name "unconnected-(J113-Pad5)") (class "Default")
      (node (ref "J113") (pin "5") (pinfunction "5_5") (pintype "passive"))
    )
    (net (code "123") (name "unconnected-(J113-Pad6)") (class "Default")
      (node (ref "J113") (pin "6") (pinfunction "6_6") (pintype "passive"))
    )
    (net (code "124") (name "unconnected-(J114-Pad1)") (class "Default")
      (node (ref "J114") (pin "1") (pinfunction "1_1") (pintype "passive"))
    )
    (net (code "125") (name "unconnected-(J114-Pad2)") (class "Default")
      (node (ref "J114") (pin "2") (pinfunction "2_2") (pintype "passive"))
    )
    (net (code "126") (name "unconnected-(J114-Pad3)") (class "Default")
      (node (ref "J114") (pin "3") (pinfunction "3_3") (pintype "passive"))
    )
    (net (code "127") (name "unconnected-(J114-Pad4)") (class "Default")
      (node (ref "J114") (pin "4") (pinfunction "4_4") (pintype "passive"))
    )
    (net (code "128") (name "unconnected-(J114-Pad5)") (class "Default")
      (node (ref "J114") (pin "5") (pinfunction "5_5") (pintype "passive"))
    )
    (net (code "129") (name "unconnected-(J114-Pad6)") (class "Default")
      (node (ref "J114") (pin "6") (pinfunction "6_6") (pintype "passive"))
    )
  )
)
